# TNY275_V1.net
KiCad netlist of a schematic drawn in Altium Designer
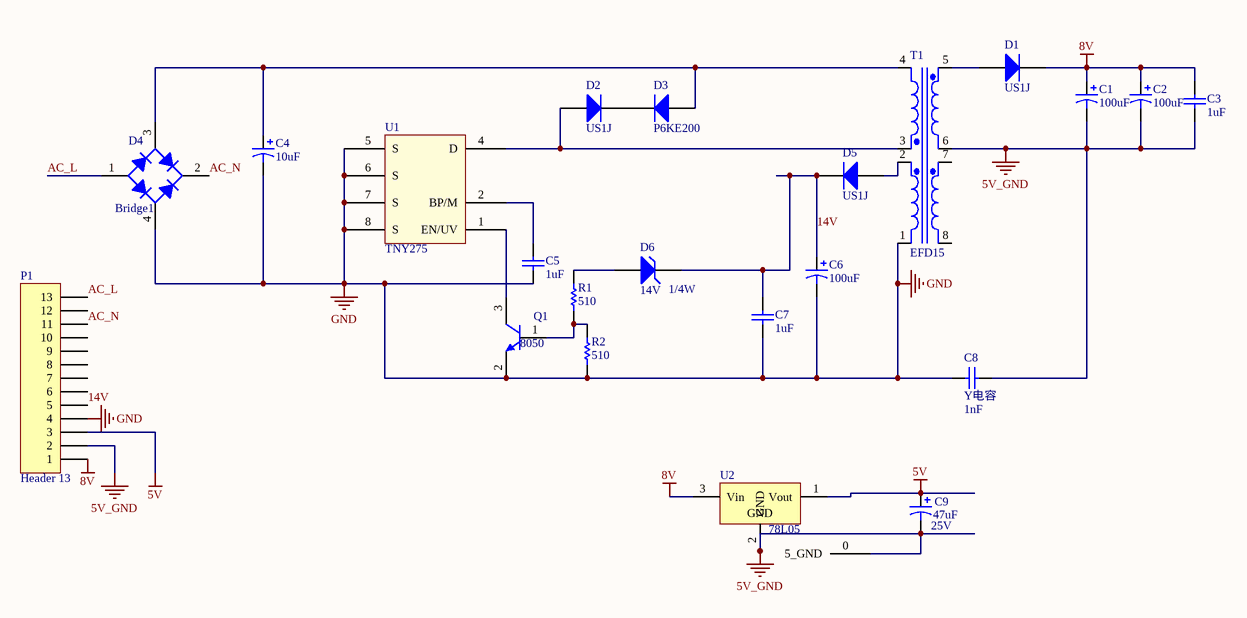
[diagram p0: TNY275_V1.SchDoc]

(export (version "E")
  (design (tool "Eeschema 10.0.6"))
  (components
    (comp (ref "C1")
      (value "100uF")
      (footprint "C-5*7")
      (description "Polarized Capacitor (Radial)")
      (fields (field (name "Comment") "Cap Pol1") (field (name "PUBLISHER") "Altium Limited"))
      (libsource (lib "Miscellaneous Devices") (part "Cap Pol1"))
    )
    (comp (ref "C2")
      (value "100uF")
      (footprint "C-5*7")
      (description "Polarized Capacitor (Radial)")
      (fields (field (name "Comment") "Cap Pol1") (field (name "PUBLISHER") "Altium Limited"))
      (libsource (lib "Miscellaneous Devices") (part "Cap Pol1"))
    )
    (comp (ref "C3")
      (value "1uF")
      (footprint "0805")
      (description "Capacitor")
      (fields (field (name "Comment") "Cap") (field (name "PUBLISHER") "Altium Limited"))
      (libsource (lib "Miscellaneous Devices") (part "Cap"))
    )
    (comp (ref "C4")
      (value "10uF")
      (footprint "C-10 卧式")
      (description "Polarized Capacitor (Radial)")
      (fields (field (name "Comment") "Cap Pol1") (field (name "PUBLISHER") "Altium Limited"))
      (libsource (lib "Miscellaneous Devices") (part "Cap Pol1"))
    )
    (comp (ref "C5")
      (value "1uF")
      (footprint "0805")
      (description "Capacitor")
      (fields (field (name "Comment") "Cap") (field (name "PUBLISHER") "Altium Limited"))
      (libsource (lib "Miscellaneous Devices") (part "Cap"))
    )
    (comp (ref "C6")
      (value "100uF")
      (footprint "电解电容6*11mm-脚距2.5mm")
      (description "Polarized Capacitor (Radial)")
      (fields (field (name "Comment") "Cap Pol1") (field (name "PUBLISHER") "Altium Limited"))
      (libsource (lib "Miscellaneous Devices") (part "Cap Pol1"))
    )
    (comp (ref "C7")
      (value "1uF")
      (footprint "0805")
      (description "Capacitor")
      (fields (field (name "Comment") "Cap") (field (name "PUBLISHER") "Altium Limited"))
      (libsource (lib "Miscellaneous Devices") (part "Cap"))
    )
    (comp (ref "C8")
      (value "Y电容")
      (footprint "07D471K")
      (description "Capacitor")
      (fields (field (name "ALTIUM_VALUE") "1nF") (field (name "PUBLISHER") "Altium Limited"))
      (libsource (lib "Miscellaneous Devices") (part "Cap"))
    )
    (comp (ref "C9")
      (value "25V")
      (footprint "1206")
      (description "Polarized Capacitor (Radial)")
      (fields (field (name "ALTIUM_VALUE") "47uF") (field (name "PUBLISHER") "Altium Limited"))
      (libsource (lib "Miscellaneous Devices") (part "Cap Pol1"))
    )
    (comp (ref "D1")
      (value "US1J")
      (footprint "SMA")
      (description "1 Amp General Purpose Rectifier")
      (fields (field (name "PUBLISHER") "Altium Limited"))
      (libsource (lib "Miscellaneous Devices") (part "Diode 1N4007"))
    )
    (comp (ref "D2")
      (value "US1J")
      (footprint "SMA")
      (description "Default Diode")
      (fields (field (name "PUBLISHER") "Altium Limited"))
      (libsource (lib "Miscellaneous Devices") (part "Diode"))
    )
    (comp (ref "D3")
      (value "P6KE200")
      (footprint "SMBJ")
      (description "Default Diode")
      (fields (field (name "PUBLISHER") "Altium Limited"))
      (libsource (lib "Miscellaneous Devices") (part "Diode"))
    )
    (comp (ref "D4")
      (value "Bridge1")
      (footprint "MB10S")
      (description "Full Wave Diode Bridge")
      (fields (field (name "PUBLISHER") "Altium Limited"))
      (libsource (lib "Miscellaneous Devices") (part "Bridge1"))
    )
    (comp (ref "D5")
      (value "US1J")
      (footprint "SMA")
      (description "1 Amp General Purpose Rectifier")
      (fields (field (name "PUBLISHER") "Altium Limited"))
      (libsource (lib "Miscellaneous Devices") (part "Diode 1N4007"))
    )
    (comp (ref "D6")
      (value "14V")
      (footprint "1206")
      (description "Zener Diode")
      (fields (field (name "A") "1/4W") (field (name "PUBLISHER") "Altium Limited"))
      (libsource (lib "Miscellaneous Devices") (part "D Zener"))
    )
    (comp (ref "P1")
      (value "Header 13")
      (footprint "2.54引脚")
      (description "Header, 13-Pin")
      (fields (field (name "PUBLISHER") "Altium Limited"))
      (libsource (lib "Miscellaneous Connectors") (part "Header 13"))
    )
    (comp (ref "Q1")
      (value "8050")
      (footprint "sot-23")
      (description "NPN Bipolar Transistor")
      (fields (field (name "PUBLISHER") "Altium Limited"))
      (libsource (lib "Miscellaneous Devices") (part "NPN"))
    )
    (comp (ref "R1")
      (value "510")
      (footprint "0805")
      (description "Resistor")
      (fields (field (name "Comment") "Res1") (field (name "PUBLISHER") "Altium Limited"))
      (libsource (lib "Miscellaneous Devices") (part "Res1"))
    )
    (comp (ref "R2")
      (value "510")
      (footprint "0805")
      (description "Resistor")
      (fields (field (name "Comment") "Res1") (field (name "PUBLISHER") "Altium Limited"))
      (libsource (lib "Miscellaneous Devices") (part "Res1"))
    )
    (comp (ref "T1") (value "EFD15") (footprint "EFD15_DIP8") (libsource (lib "YGT_01") (part "EFD15")))
    (comp (ref "U1") (value "TNY275") (footprint "TNY275_SMD") (libsource (lib "YGT_01") (part "TNY275")))
    (comp (ref "U2")
      (value "78L05")
      (footprint "Miscellaneous Devices:SOT89")
      (description "Voltage Regulator")
      (fields (field (name "PUBLISHER") "Altium Limited"))
      (libsource (lib "Miscellaneous Devices") (part "Volt Reg"))
    )
  )
  (nets
    (net (code "1") (name "/14V") (class "Default")
      (node (ref "C6") (pin "1") (pinfunction "1_1") (pintype "passive"))
      (node (ref "C7") (pin "2") (pinfunction "2_2") (pintype "passive"))
      (node (ref "D5") (pin "2") (pinfunction "K_2") (pintype "passive"))
      (node (ref "D6") (pin "2") (pinfunction "K_2") (pintype "passive"))
      (node (ref "P1") (pin "5") (pinfunction "5_5") (pintype "passive"))
    )
    (net (code "2") (name "/AC_L") (class "Default")
      (node (ref "D4") (pin "1") (pinfunction "AC_1") (pintype "passive"))
      (node (ref "P1") (pin "13") (pinfunction "13_13") (pintype "passive"))
    )
    (net (code "3") (name "/AC_N") (class "Default")
      (node (ref "D4") (pin "2") (pinfunction "AC_2") (pintype "passive"))
      (node (ref "P1") (pin "11") (pinfunction "11_11") (pintype "passive"))
    )
    (net (code "4") (name "5V") (class "Default")
      (node (ref "C9") (pin "1") (pinfunction "1_1") (pintype "passive"))
      (node (ref "P1") (pin "3") (pinfunction "3_3") (pintype "passive"))
      (node (ref "U2") (pin "1") (pinfunction "Vout_1") (pintype "passive"))
    )
    (net (code "5") (name "5V_GND") (class "Default")
      (node (ref "C1") (pin "2") (pinfunction "2_2") (pintype "passive"))
      (node (ref "C2") (pin "2") (pinfunction "2_2") (pintype "passive"))
      (node (ref "C3") (pin "1") (pinfunction "1_1") (pintype "passive"))
      (node (ref "C8") (pin "2") (pinfunction "2_2") (pintype "passive"))
      (node (ref "C9") (pin "2") (pinfunction "2_2") (pintype "passive"))
      (node (ref "P1") (pin "2") (pinfunction "2_2") (pintype "passive"))
      (node (ref "T1") (pin "6") (pinfunction "Sec1-_6") (pintype "passive"))
      (node (ref "U2") (pin "0") (pinfunction "5_GND_0") (pintype "passive"))
      (node (ref "U2") (pin "2") (pinfunction "GND_2") (pintype "passive"))
    )
    (net (code "6") (name "8V") (class "Default")
      (node (ref "C1") (pin "1") (pinfunction "1_1") (pintype "passive"))
      (node (ref "C2") (pin "1") (pinfunction "1_1") (pintype "passive"))
      (node (ref "C3") (pin "2") (pinfunction "2_2") (pintype "passive"))
      (node (ref "D1") (pin "2") (pinfunction "K_2") (pintype "passive"))
      (node (ref "P1") (pin "1") (pinfunction "1_1") (pintype "passive"))
      (node (ref "U2") (pin "3") (pinfunction "Vin_3") (pintype "passive"))
    )
    (net (code "7") (name "GND") (class "Default")
      (node (ref "C4") (pin "2") (pinfunction "2_2") (pintype "passive"))
      (node (ref "C5") (pin "1") (pinfunction "1_1") (pintype "passive"))
      (node (ref "C6") (pin "2") (pinfunction "2_2") (pintype "passive"))
      (node (ref "C7") (pin "1") (pinfunction "1_1") (pintype "passive"))
      (node (ref "C8") (pin "1") (pinfunction "1_1") (pintype "passive"))
      (node (ref "D4") (pin "4") (pinfunction "-_4") (pintype "passive"))
      (node (ref "P1") (pin "4") (pinfunction "4_4") (pintype "passive"))
      (node (ref "Q1") (pin "2") (pinfunction "E_2") (pintype "passive"))
      (node (ref "R2") (pin "2") (pinfunction "2_2") (pintype "passive"))
      (node (ref "T1") (pin "1") (pinfunction "Pri2-_1") (pintype "passive"))
      (node (ref "U1") (pin "5") (pinfunction "S_5") (pintype "passive"))
      (node (ref "U1") (pin "6") (pinfunction "S_6") (pintype "passive"))
      (node (ref "U1") (pin "7") (pinfunction "S_7") (pintype "passive"))
      (node (ref "U1") (pin "8") (pinfunction "S_8") (pintype "passive"))
    )
    (net (code "8") (name "Net-(D1-A)") (class "Default")
      (node (ref "D1") (pin "1") (pinfunction "A_1") (pintype "passive"))
      (node (ref "T1") (pin "5") (pinfunction "Sec1+_5") (pintype "passive"))
    )
    (net (code "9") (name "Net-(D2-A)") (class "Default")
      (node (ref "D2") (pin "1") (pinfunction "A_1") (pintype "passive"))
      (node (ref "T1") (pin "3") (pinfunction "Pri1-_3") (pintype "passive"))
      (node (ref "U1") (pin "4") (pinfunction "D_4") (pintype "passive"))
    )
    (net (code "10") (name "Net-(D2-K)") (class "Default")
      (node (ref "D2") (pin "2") (pinfunction "K_2") (pintype "passive"))
      (node (ref "D3") (pin "2") (pinfunction "K_2") (pintype "passive"))
    )
    (net (code "11") (name "Net-(D3-A)") (class "Default")
      (node (ref "C4") (pin "1") (pinfunction "1_1") (pintype "passive"))
      (node (ref "D3") (pin "1") (pinfunction "A_1") (pintype "passive"))
      (node (ref "D4") (pin "3") (pinfunction "+_3") (pintype "passive"))
      (node (ref "T1") (pin "4") (pinfunction "Pri1+_4") (pintype "passive"))
    )
    (net (code "12") (name "Net-(D5-A)") (class "Default")
      (node (ref "D5") (pin "1") (pinfunction "A_1") (pintype "passive"))
      (node (ref "T1") (pin "2") (pinfunction "Pri2+_2") (pintype "passive"))
    )
    (net (code "13") (name "Net-(D6-A)") (class "Default")
      (node (ref "D6") (pin "1") (pinfunction "A_1") (pintype "passive"))
      (node (ref "R1") (pin "1") (pinfunction "1_1") (pintype "passive"))
    )
    (net (code "14") (name "Net-(Q1-B)") (class "Default")
      (node (ref "Q1") (pin "1") (pinfunction "B_1") (pintype "passive"))
      (node (ref "R1") (pin "2") (pinfunction "2_2") (pintype "passive"))
      (node (ref "R2") (pin "1") (pinfunction "1_1") (pintype "passive"))
    )
    (net (code "15") (name "Net-(Q1-C)") (class "Default")
      (node (ref "Q1") (pin "3") (pinfunction "C_3") (pintype "passive"))
      (node (ref "U1") (pin "1") (pinfunction "EN/UV_1") (pintype "passive"))
    )
    (net (code "16") (name "Net-(U1-BP{slash}M)") (class "Default")
      (node (ref "C5") (pin "2") (pinfunction "2_2") (pintype "passive"))
      (node (ref "U1") (pin "2") (pinfunction "BP/M_2") (pintype "passive"))
    )
    (net (code "17") (name "unconnected-(P1-Pad6)") (class "Default")
      (node (ref "P1") (pin "6") (pinfunction "6_6") (pintype "passive"))
    )
    (net (code "18") (name "unconnected-(P1-Pad7)") (class "Default")
      (node (ref "P1") (pin "7") (pinfunction "7_7") (pintype "passive"))
    )
    (net (code "19") (name "unconnected-(P1-Pad8)") (class "Default")
      (node (ref "P1") (pin "8") (pinfunction "8_8") (pintype "passive"))
    )
    (net (code "20") (name "unconnected-(P1-Pad9)") (class "Default")
      (node (ref "P1") (pin "9") (pinfunction "9_9") (pintype "passive"))
    )
    (net (code "21") (name "unconnected-(P1-Pad10)") (class "Default")
      (node (ref "P1") (pin "10") (pinfunction "10_10") (pintype "passive"))
    )
    (net (code "22") (name "unconnected-(P1-Pad12)") (class "Default")
      (node (ref "P1") (pin "12") (pinfunction "12_12") (pintype "passive"))
    )
    (net (code "23") (name "unconnected-(T1-Sec2+-Pad7)") (class "Default")
      (node (ref "T1") (pin "7") (pinfunction "Sec2+_7") (pintype "passive"))
    )
    (net (code "24") (name "unconnected-(T1-Sec2--Pad8)") (class "Default")
      (node (ref "T1") (pin "8") (pinfunction "Sec2-_8") (pintype "passive"))
    )
  )
)
